# Master.net
KiCad netlist of a schematic drawn in EAGLE
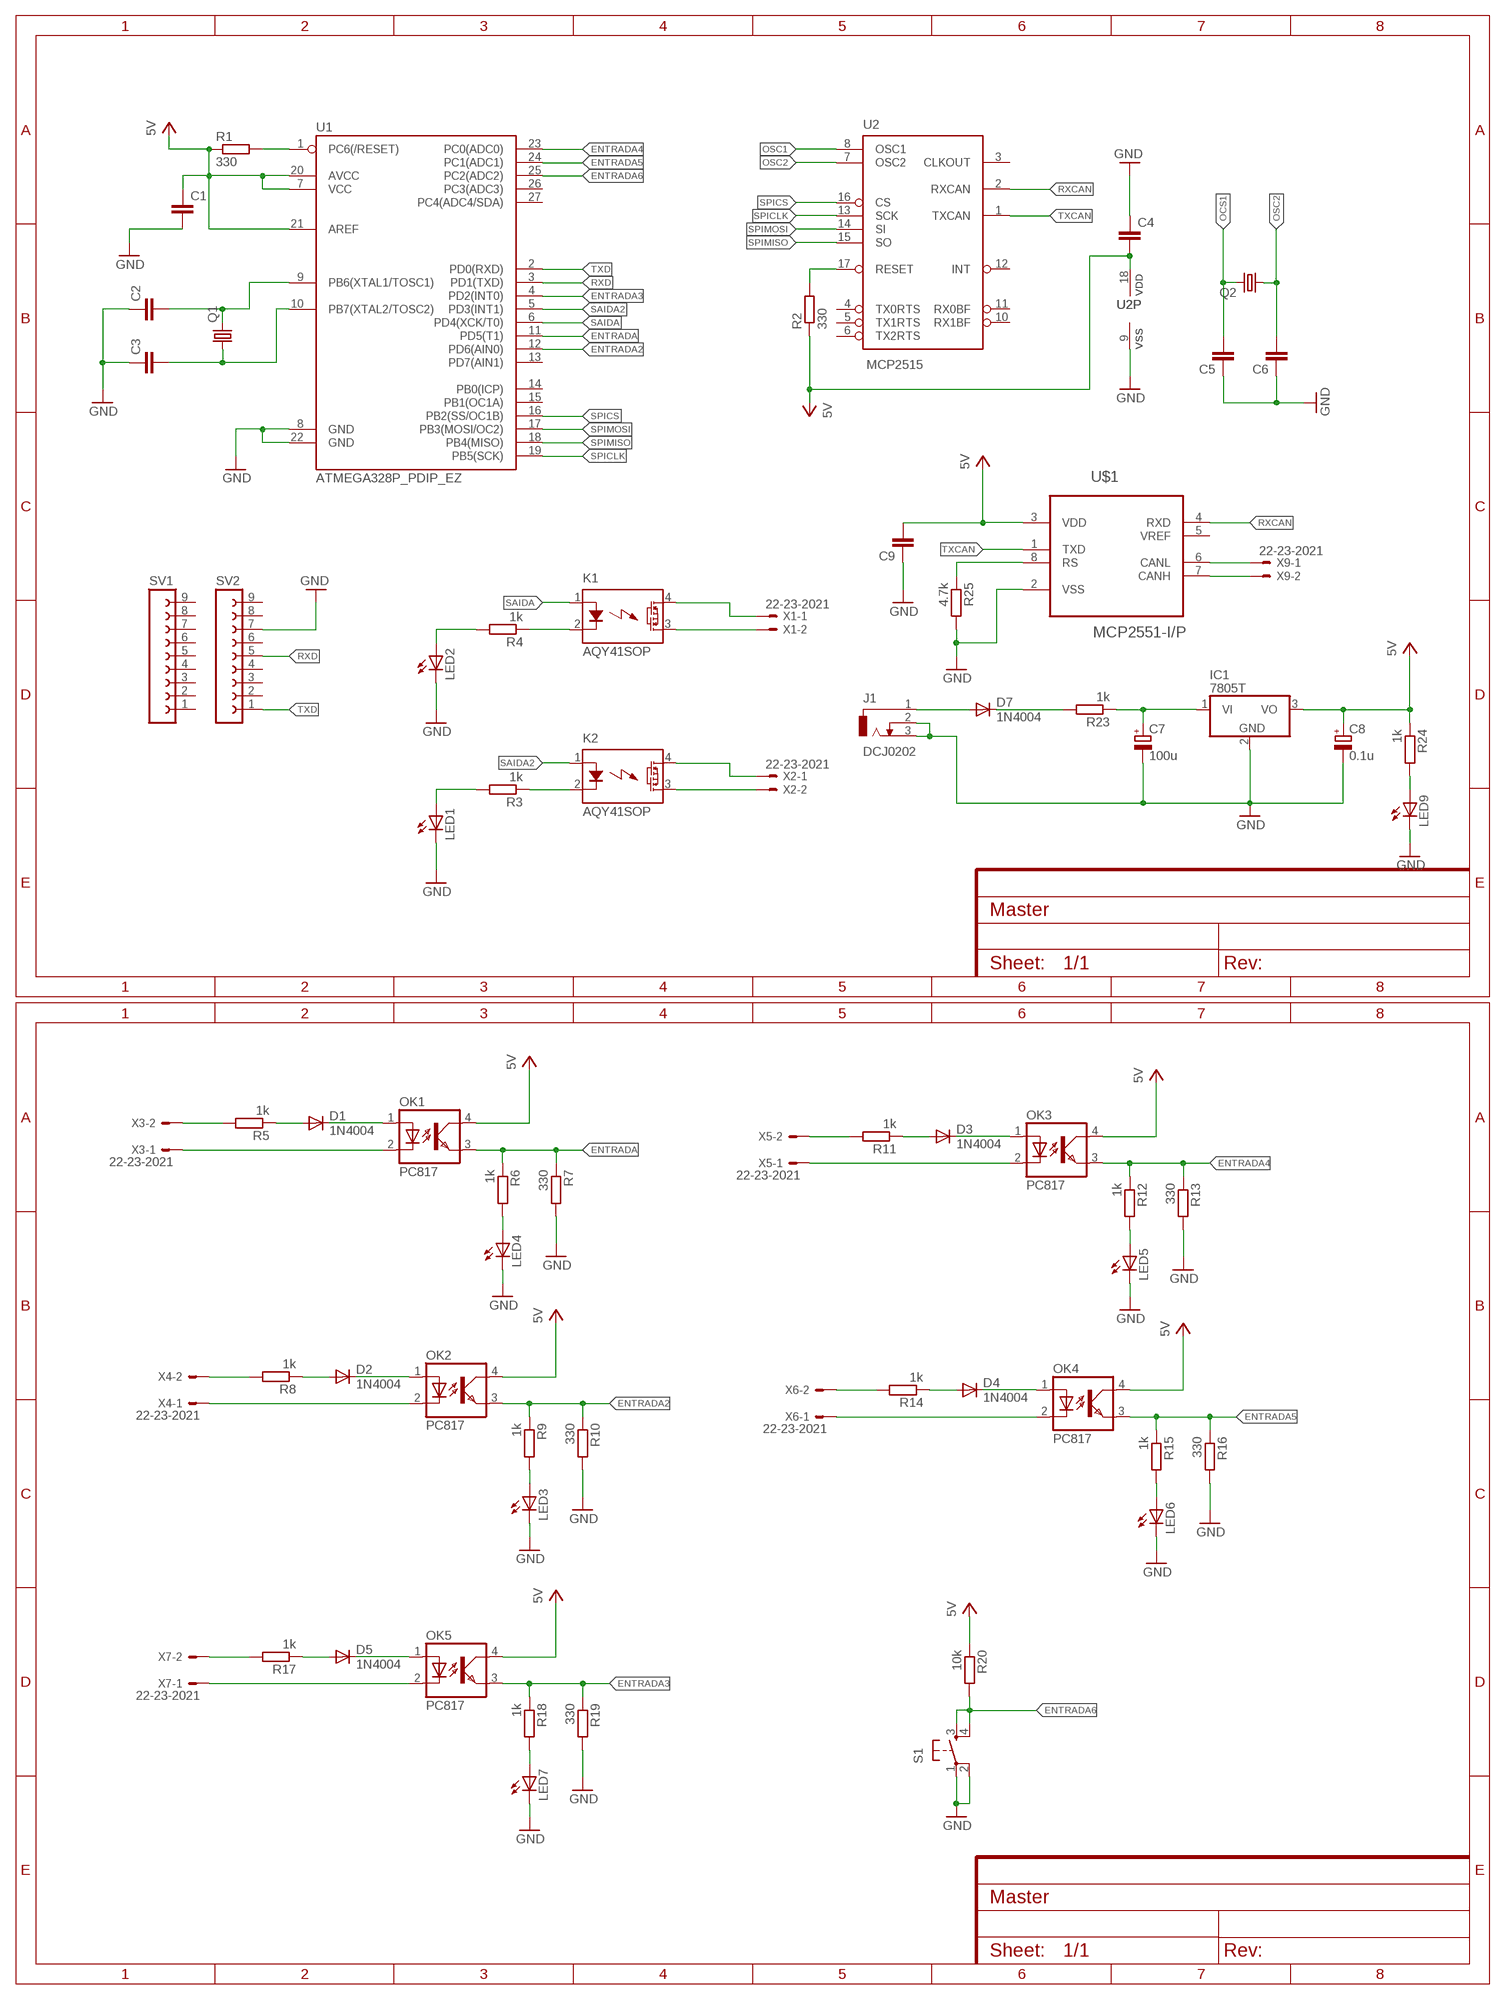
[diagram p0: schematic, sheet 1]

(export (version "E")
  (design (tool "Eeschema 10.0.6"))
  (components
    (comp (ref "C1")
      (value "C2,5-3")
      (footprint "eagle-import:C2.5-3")
      (libsource (lib "eagle-import") (part "C2,5-3"))
    )
    (comp (ref "C2")
      (value "C2,5-3")
      (footprint "eagle-import:C2.5-3")
      (libsource (lib "eagle-import") (part "C2,5-3"))
    )
    (comp (ref "C3")
      (value "C2,5-3")
      (footprint "eagle-import:C2.5-3")
      (libsource (lib "eagle-import") (part "C2,5-3"))
    )
    (comp (ref "C4")
      (value "C2,5-3")
      (footprint "eagle-import:C2.5-3")
      (libsource (lib "eagle-import") (part "C2,5-3"))
    )
    (comp (ref "C5")
      (value "C2,5-3")
      (footprint "eagle-import:C2.5-3")
      (libsource (lib "eagle-import") (part "C2,5-3"))
    )
    (comp (ref "C6")
      (value "C2,5-3")
      (footprint "eagle-import:C2.5-3")
      (libsource (lib "eagle-import") (part "C2,5-3"))
    )
    (comp (ref "C7")
      (value "100u")
      (footprint "eagle-import:E2,5-6")
      (libsource (lib "eagle-import") (part "CPOL-EUE2.5-6"))
    )
    (comp (ref "C8")
      (value "0.1u")
      (footprint "eagle-import:E2,5-6")
      (libsource (lib "eagle-import") (part "CPOL-EUE2.5-6"))
    )
    (comp (ref "C9")
      (value "C2,5-3")
      (footprint "eagle-import:C2.5-3")
      (libsource (lib "eagle-import") (part "C2,5-3"))
    )
    (comp (ref "D1")
      (value "1N4004")
      (footprint "eagle-import:DO41-10")
      (libsource (lib "eagle-import") (part "1N4004"))
    )
    (comp (ref "D2")
      (value "1N4004")
      (footprint "eagle-import:DO41-10")
      (libsource (lib "eagle-import") (part "1N4004"))
    )
    (comp (ref "D3")
      (value "1N4004")
      (footprint "eagle-import:DO41-10")
      (libsource (lib "eagle-import") (part "1N4004"))
    )
    (comp (ref "D4")
      (value "1N4004")
      (footprint "eagle-import:DO41-10")
      (libsource (lib "eagle-import") (part "1N4004"))
    )
    (comp (ref "D5")
      (value "1N4004")
      (footprint "eagle-import:DO41-10")
      (libsource (lib "eagle-import") (part "1N4004"))
    )
    (comp (ref "D7")
      (value "1N4004")
      (footprint "eagle-import:DO41-10")
      (libsource (lib "eagle-import") (part "1N4004"))
    )
    (comp (ref "IC1")
      (value "7805T")
      (footprint "eagle-import:TO220H")
      (libsource (lib "eagle-import") (part "78T05"))
    )
    (comp (ref "J1")
      (value "DCJ0202")
      (footprint "eagle-import:DCJ0202")
      (libsource (lib "eagle-import") (part "DCJ0202"))
    )
    (comp (ref "K1")
      (value "AQY41SOP")
      (footprint "eagle-import:SOP04")
      (libsource (lib "eagle-import") (part "AQYSOP41"))
    )
    (comp (ref "K2")
      (value "AQY41SOP")
      (footprint "eagle-import:SOP04")
      (libsource (lib "eagle-import") (part "AQYSOP41"))
    )
    (comp (ref "LED1")
      (value "LED_ELD260")
      (footprint "eagle-import:LED_LD260")
      (libsource (lib "eagle-import") (part "LED_ELD260"))
    )
    (comp (ref "LED2")
      (value "LED_ELD260")
      (footprint "eagle-import:LED_LD260")
      (libsource (lib "eagle-import") (part "LED_ELD260"))
    )
    (comp (ref "LED3")
      (value "LED_ELD260")
      (footprint "eagle-import:LED_LD260")
      (libsource (lib "eagle-import") (part "LED_ELD260"))
    )
    (comp (ref "LED4")
      (value "LED_ELD260")
      (footprint "eagle-import:LED_LD260")
      (libsource (lib "eagle-import") (part "LED_ELD260"))
    )
    (comp (ref "LED5")
      (value "LED_ELD260")
      (footprint "eagle-import:LED_LD260")
      (libsource (lib "eagle-import") (part "LED_ELD260"))
    )
    (comp (ref "LED6")
      (value "LED_ELD260")
      (footprint "eagle-import:LED_LD260")
      (libsource (lib "eagle-import") (part "LED_ELD260"))
    )
    (comp (ref "LED7")
      (value "LED_ELD260")
      (footprint "eagle-import:LED_LD260")
      (libsource (lib "eagle-import") (part "LED_ELD260"))
    )
    (comp (ref "LED9")
      (value "LED_ELD260")
      (footprint "eagle-import:LED_LD260")
      (libsource (lib "eagle-import") (part "LED_ELD260"))
    )
    (comp (ref "OK1")
      (value "PC817")
      (footprint "eagle-import:DIL04")
      (fields (field (name "MPN") "PC817X4J000F"))
      (libsource (lib "eagle-import") (part "PC817"))
    )
    (comp (ref "OK2")
      (value "PC817")
      (footprint "eagle-import:DIL04")
      (fields (field (name "MPN") "PC817X4J000F"))
      (libsource (lib "eagle-import") (part "PC817"))
    )
    (comp (ref "OK3")
      (value "PC817")
      (footprint "eagle-import:DIL04")
      (fields (field (name "MPN") "PC817X4J000F"))
      (libsource (lib "eagle-import") (part "PC817"))
    )
    (comp (ref "OK4")
      (value "PC817")
      (footprint "eagle-import:DIL04")
      (fields (field (name "MPN") "PC817X4J000F"))
      (libsource (lib "eagle-import") (part "PC817"))
    )
    (comp (ref "OK5")
      (value "PC817")
      (footprint "eagle-import:DIL04")
      (fields (field (name "MPN") "PC817X4J000F"))
      (libsource (lib "eagle-import") (part "PC817"))
    )
    (comp (ref "Q1")
      (value "CRYSTALHC49U70")
      (footprint "eagle-import:HC49U70")
      (libsource (lib "eagle-import") (part "CRYSTALHC49U70"))
    )
    (comp (ref "Q2")
      (value "CRYSTALHC49U70")
      (footprint "eagle-import:HC49U70")
      (libsource (lib "eagle-import") (part "CRYSTALHC49U70"))
    )
    (comp (ref "R1")
      (value "330")
      (footprint "eagle-import:0204_5")
      (libsource (lib "eagle-import") (part "R-EU_0204/5"))
    )
    (comp (ref "R2")
      (value "330")
      (footprint "eagle-import:0204_5")
      (libsource (lib "eagle-import") (part "R-EU_0204/5"))
    )
    (comp (ref "R3")
      (value "1k")
      (footprint "eagle-import:0204_5")
      (libsource (lib "eagle-import") (part "R-EU_0204/5"))
    )
    (comp (ref "R4")
      (value "1k")
      (footprint "eagle-import:0204_5")
      (libsource (lib "eagle-import") (part "R-EU_0204/5"))
    )
    (comp (ref "R5")
      (value "1k")
      (footprint "eagle-import:0204_5")
      (libsource (lib "eagle-import") (part "R-EU_0204/5"))
    )
    (comp (ref "R6")
      (value "1k")
      (footprint "eagle-import:0204_5")
      (libsource (lib "eagle-import") (part "R-EU_0204/5"))
    )
    (comp (ref "R7")
      (value "330")
      (footprint "eagle-import:0204_5")
      (libsource (lib "eagle-import") (part "R-EU_0204/5"))
    )
    (comp (ref "R8")
      (value "1k")
      (footprint "eagle-import:0204_5")
      (libsource (lib "eagle-import") (part "R-EU_0204/5"))
    )
    (comp (ref "R9")
      (value "1k")
      (footprint "eagle-import:0204_5")
      (libsource (lib "eagle-import") (part "R-EU_0204/5"))
    )
    (comp (ref "R10")
      (value "330")
      (footprint "eagle-import:0204_5")
      (libsource (lib "eagle-import") (part "R-EU_0204/5"))
    )
    (comp (ref "R11")
      (value "1k")
      (footprint "eagle-import:0204_5")
      (libsource (lib "eagle-import") (part "R-EU_0204/5"))
    )
    (comp (ref "R12")
      (value "1k")
      (footprint "eagle-import:0204_5")
      (libsource (lib "eagle-import") (part "R-EU_0204/5"))
    )
    (comp (ref "R13")
      (value "330")
      (footprint "eagle-import:0204_5")
      (libsource (lib "eagle-import") (part "R-EU_0204/5"))
    )
    (comp (ref "R14")
      (value "1k")
      (footprint "eagle-import:0204_5")
      (libsource (lib "eagle-import") (part "R-EU_0204/5"))
    )
    (comp (ref "R15")
      (value "1k")
      (footprint "eagle-import:0204_5")
      (libsource (lib "eagle-import") (part "R-EU_0204/5"))
    )
    (comp (ref "R16")
      (value "330")
      (footprint "eagle-import:0204_5")
      (libsource (lib "eagle-import") (part "R-EU_0204/5"))
    )
    (comp (ref "R17")
      (value "1k")
      (footprint "eagle-import:0204_5")
      (libsource (lib "eagle-import") (part "R-EU_0204/5"))
    )
    (comp (ref "R18")
      (value "1k")
      (footprint "eagle-import:0204_5")
      (libsource (lib "eagle-import") (part "R-EU_0204/5"))
    )
    (comp (ref "R19")
      (value "330")
      (footprint "eagle-import:0204_5")
      (libsource (lib "eagle-import") (part "R-EU_0204/5"))
    )
    (comp (ref "R20")
      (value "10k")
      (footprint "eagle-import:0204_5")
      (libsource (lib "eagle-import") (part "R-EU_0204/5"))
    )
    (comp (ref "R23")
      (value "1k")
      (footprint "eagle-import:0204_5")
      (libsource (lib "eagle-import") (part "R-EU_0204/5"))
    )
    (comp (ref "R24")
      (value "1k")
      (footprint "eagle-import:0204_5")
      (libsource (lib "eagle-import") (part "R-EU_0204/5"))
    )
    (comp (ref "R25")
      (value "4.7k")
      (footprint "eagle-import:0204_5")
      (libsource (lib "eagle-import") (part "R-EU_0204/5"))
    )
    (comp (ref "S1")
      (value "TAC_SWITCHPTH")
      (footprint "eagle-import:TACTILE-PTH")
      (libsource (lib "eagle-import") (part "TAC_SWITCHPTH"))
    )
    (comp (ref "SV1")
      (value "FE09-1")
      (footprint "eagle-import:FE09")
      (libsource (lib "eagle-import") (part "FE09-1"))
    )
    (comp (ref "SV2")
      (value "FE09-1")
      (footprint "eagle-import:FE09")
      (libsource (lib "eagle-import") (part "FE09-1"))
    )
    (comp (ref "U$1")
      (value "MCP2551-I/P")
      (footprint "eagle-import:DIP254P762X432-8")
      (libsource (lib "eagle-import") (part "MCP2551-I/P"))
    )
    (comp (ref "U1")
      (value "ATMEGA328P_PDIP_EZ")
      (footprint "eagle-import:DIP28-SIMON-KIT")
      (libsource (lib "eagle-import") (part "ATMEGA328P_PDIP_EZ"))
    )
    (comp (ref "U2")
      (value "MCP2515")
      (footprint "eagle-import:DIP18")
      (libsource (lib "eagle-import") (part "MCP2515(MCP2510)P"))
    )
    (comp (ref "X1")
      (value "22-23-2021")
      (footprint "eagle-import:22-23-2021")
      (fields (field (name "MF") "MOLEX"))
      (libsource (lib "eagle-import") (part "22-23-2021"))
    )
    (comp (ref "X2")
      (value "22-23-2021")
      (footprint "eagle-import:22-23-2021")
      (fields (field (name "MF") "MOLEX"))
      (libsource (lib "eagle-import") (part "22-23-2021"))
    )
    (comp (ref "X3")
      (value "22-23-2021")
      (footprint "eagle-import:22-23-2021")
      (fields (field (name "MF") "MOLEX"))
      (libsource (lib "eagle-import") (part "22-23-2021"))
    )
    (comp (ref "X4")
      (value "22-23-2021")
      (footprint "eagle-import:22-23-2021")
      (fields (field (name "MF") "MOLEX"))
      (libsource (lib "eagle-import") (part "22-23-2021"))
    )
    (comp (ref "X5")
      (value "22-23-2021")
      (footprint "eagle-import:22-23-2021")
      (fields (field (name "MF") "MOLEX"))
      (libsource (lib "eagle-import") (part "22-23-2021"))
    )
    (comp (ref "X6")
      (value "22-23-2021")
      (footprint "eagle-import:22-23-2021")
      (fields (field (name "MF") "MOLEX"))
      (libsource (lib "eagle-import") (part "22-23-2021"))
    )
    (comp (ref "X7")
      (value "22-23-2021")
      (footprint "eagle-import:22-23-2021")
      (fields (field (name "MF") "MOLEX"))
      (libsource (lib "eagle-import") (part "22-23-2021"))
    )
    (comp (ref "X9")
      (value "22-23-2021")
      (footprint "eagle-import:22-23-2021")
      (fields (field (name "MF") "MOLEX"))
      (libsource (lib "eagle-import") (part "22-23-2021"))
    )
  )
  (nets
    (net (code "1") (name "5V") (class "Default")
      (node (ref "C1") (pin "1") (pinfunction "1_1") (pintype "passive"))
      (node (ref "C4") (pin "2") (pinfunction "2_2") (pintype "passive"))
      (node (ref "C8") (pin "+") (pinfunction "+_+") (pintype "passive"))
      (node (ref "C9") (pin "2") (pinfunction "2_2") (pintype "passive"))
      (node (ref "IC1") (pin "3") (pinfunction "VO_3") (pintype "passive"))
      (node (ref "OK1") (pin "4") (pinfunction "COL_4") (pintype "passive"))
      (node (ref "OK2") (pin "4") (pinfunction "COL_4") (pintype "passive"))
      (node (ref "OK3") (pin "4") (pinfunction "COL_4") (pintype "passive"))
      (node (ref "OK4") (pin "4") (pinfunction "COL_4") (pintype "passive"))
      (node (ref "OK5") (pin "4") (pinfunction "COL_4") (pintype "passive"))
      (node (ref "R1") (pin "1") (pinfunction "1_1") (pintype "passive"))
      (node (ref "R2") (pin "1") (pinfunction "1_1") (pintype "passive"))
      (node (ref "R20") (pin "1") (pinfunction "1_1") (pintype "passive"))
      (node (ref "R24") (pin "1") (pinfunction "1_1") (pintype "passive"))
      (node (ref "U$1") (pin "3") (pinfunction "VDD_3") (pintype "power_in"))
      (node (ref "U1") (pin "20") (pinfunction "AVCC_20") (pintype "bidirectional"))
      (node (ref "U1") (pin "21") (pinfunction "AREF_21") (pintype "bidirectional"))
      (node (ref "U1") (pin "7") (pinfunction "VCC_7") (pintype "bidirectional"))
      (node (ref "U2") (pin "18") (pinfunction "VDD_18") (pintype "power_in"))
    )
    (net (code "2") (name "ENTRADA") (class "Default")
      (node (ref "OK1") (pin "3") (pinfunction "EMIT_3") (pintype "passive"))
      (node (ref "R6") (pin "1") (pinfunction "1_1") (pintype "passive"))
      (node (ref "R7") (pin "1") (pinfunction "1_1") (pintype "passive"))
      (node (ref "U1") (pin "11") (pinfunction "PD5(T1)_11") (pintype "bidirectional"))
    )
    (net (code "3") (name "ENTRADA2") (class "Default")
      (node (ref "OK2") (pin "3") (pinfunction "EMIT_3") (pintype "passive"))
      (node (ref "R10") (pin "1") (pinfunction "1_1") (pintype "passive"))
      (node (ref "R9") (pin "1") (pinfunction "1_1") (pintype "passive"))
      (node (ref "U1") (pin "12") (pinfunction "PD6(AIN0)_12") (pintype "bidirectional"))
    )
    (net (code "4") (name "ENTRADA3") (class "Default")
      (node (ref "OK5") (pin "3") (pinfunction "EMIT_3") (pintype "passive"))
      (node (ref "R18") (pin "1") (pinfunction "1_1") (pintype "passive"))
      (node (ref "R19") (pin "1") (pinfunction "1_1") (pintype "passive"))
      (node (ref "U1") (pin "4") (pinfunction "PD2(INT0)_4") (pintype "bidirectional"))
    )
    (net (code "5") (name "ENTRADA4") (class "Default")
      (node (ref "OK3") (pin "3") (pinfunction "EMIT_3") (pintype "passive"))
      (node (ref "R12") (pin "1") (pinfunction "1_1") (pintype "passive"))
      (node (ref "R13") (pin "1") (pinfunction "1_1") (pintype "passive"))
      (node (ref "U1") (pin "23") (pinfunction "PC0(ADC0)_23") (pintype "bidirectional"))
    )
    (net (code "6") (name "ENTRADA5") (class "Default")
      (node (ref "OK4") (pin "3") (pinfunction "EMIT_3") (pintype "passive"))
      (node (ref "R15") (pin "1") (pinfunction "1_1") (pintype "passive"))
      (node (ref "R16") (pin "1") (pinfunction "1_1") (pintype "passive"))
      (node (ref "U1") (pin "24") (pinfunction "PC1(ADC1)_24") (pintype "bidirectional"))
    )
    (net (code "7") (name "ENTRADA6") (class "Default")
      (node (ref "R20") (pin "2") (pinfunction "2_2") (pintype "passive"))
      (node (ref "S1") (pin "3") (pinfunction "3_3") (pintype "passive"))
      (node (ref "S1") (pin "4") (pinfunction "4_4") (pintype "passive"))
      (node (ref "U1") (pin "25") (pinfunction "PC2(ADC2)_25") (pintype "bidirectional"))
    )
    (net (code "8") (name "GND") (class "Default")
      (node (ref "C1") (pin "2") (pinfunction "2_2") (pintype "passive"))
      (node (ref "C2") (pin "1") (pinfunction "1_1") (pintype "passive"))
      (node (ref "C3") (pin "1") (pinfunction "1_1") (pintype "passive"))
      (node (ref "C4") (pin "1") (pinfunction "1_1") (pintype "passive"))
      (node (ref "C5") (pin "1") (pinfunction "1_1") (pintype "passive"))
      (node (ref "C6") (pin "1") (pinfunction "1_1") (pintype "passive"))
      (node (ref "C7") (pin "-") (pinfunction "-_-") (pintype "passive"))
      (node (ref "C8") (pin "-") (pinfunction "-_-") (pintype "passive"))
      (node (ref "C9") (pin "1") (pinfunction "1_1") (pintype "passive"))
      (node (ref "IC1") (pin "2") (pinfunction "GND_2") (pintype "passive"))
      (node (ref "J1") (pin "2") (pinfunction "2_2") (pintype "passive"))
      (node (ref "J1") (pin "3") (pinfunction "3_3") (pintype "passive"))
      (node (ref "LED1") (pin "K") (pinfunction "C_K") (pintype "passive"))
      (node (ref "LED2") (pin "K") (pinfunction "C_K") (pintype "passive"))
      (node (ref "LED3") (pin "K") (pinfunction "C_K") (pintype "passive"))
      (node (ref "LED4") (pin "K") (pinfunction "C_K") (pintype "passive"))
      (node (ref "LED5") (pin "K") (pinfunction "C_K") (pintype "passive"))
      (node (ref "LED6") (pin "K") (pinfunction "C_K") (pintype "passive"))
      (node (ref "LED7") (pin "K") (pinfunction "C_K") (pintype "passive"))
      (node (ref "LED9") (pin "K") (pinfunction "C_K") (pintype "passive"))
      (node (ref "R10") (pin "2") (pinfunction "2_2") (pintype "passive"))
      (node (ref "R13") (pin "2") (pinfunction "2_2") (pintype "passive"))
      (node (ref "R16") (pin "2") (pinfunction "2_2") (pintype "passive"))
      (node (ref "R19") (pin "2") (pinfunction "2_2") (pintype "passive"))
      (node (ref "R25") (pin "2") (pinfunction "2_2") (pintype "passive"))
      (node (ref "R7") (pin "2") (pinfunction "2_2") (pintype "passive"))
      (node (ref "S1") (pin "1") (pinfunction "1_1") (pintype "passive"))
      (node (ref "S1") (pin "2") (pinfunction "2_2") (pintype "passive"))
      (node (ref "SV2") (pin "7") (pinfunction "7_7") (pintype "passive"))
      (node (ref "U$1") (pin "2") (pinfunction "VSS_2") (pintype "power_in"))
      (node (ref "U1") (pin "22") (pinfunction "GND_22") (pintype "bidirectional"))
      (node (ref "U1") (pin "8") (pinfunction "GND_8") (pintype "bidirectional"))
      (node (ref "U2") (pin "9") (pinfunction "VSS_9") (pintype "power_in"))
    )
    (net (code "9") (name "Net-(D1-PadA)") (class "Default")
      (node (ref "D1") (pin "A") (pinfunction "A_A") (pintype "passive"))
      (node (ref "R5") (pin "1") (pinfunction "1_1") (pintype "passive"))
    )
    (net (code "10") (name "Net-(D2-PadA)") (class "Default")
      (node (ref "D2") (pin "A") (pinfunction "A_A") (pintype "passive"))
      (node (ref "R8") (pin "1") (pinfunction "1_1") (pintype "passive"))
    )
    (net (code "11") (name "Net-(D3-PadA)") (class "Default")
      (node (ref "D3") (pin "A") (pinfunction "A_A") (pintype "passive"))
      (node (ref "R11") (pin "1") (pinfunction "1_1") (pintype "passive"))
    )
    (net (code "12") (name "Net-(D4-PadA)") (class "Default")
      (node (ref "D4") (pin "A") (pinfunction "A_A") (pintype "passive"))
      (node (ref "R14") (pin "1") (pinfunction "1_1") (pintype "passive"))
    )
    (net (code "13") (name "Net-(D5-PadA)") (class "Default")
      (node (ref "D5") (pin "A") (pinfunction "A_A") (pintype "passive"))
      (node (ref "R17") (pin "1") (pinfunction "1_1") (pintype "passive"))
    )
    (net (code "14") (name "Net-(D7-PadA)") (class "Default")
      (node (ref "D7") (pin "A") (pinfunction "A_A") (pintype "passive"))
      (node (ref "J1") (pin "1") (pinfunction "1_1") (pintype "passive"))
    )
    (net (code "15") (name "Net-(D7-PadC)") (class "Default")
      (node (ref "D7") (pin "C") (pinfunction "C_C") (pintype "passive"))
      (node (ref "R23") (pin "2") (pinfunction "2_2") (pintype "passive"))
    )
    (net (code "16") (name "Net-(IC1-VI)") (class "Default")
      (node (ref "C7") (pin "+") (pinfunction "+_+") (pintype "passive"))
      (node (ref "IC1") (pin "1") (pinfunction "VI_1") (pintype "input"))
      (node (ref "R23") (pin "1") (pinfunction "1_1") (pintype "passive"))
    )
    (net (code "17") (name "Net-(K1-DS1)") (class "Default")
      (node (ref "K1") (pin "4") (pinfunction "DS1_4") (pintype "passive"))
      (node (ref "X1") (pin "1") (pinfunction "S_1") (pintype "passive"))
    )
    (net (code "18") (name "Net-(K1-DS2)") (class "Default")
      (node (ref "K1") (pin "3") (pinfunction "DS2_3") (pintype "passive"))
      (node (ref "X1") (pin "2") (pinfunction "S_2") (pintype "passive"))
    )
    (net (code "19") (name "Net-(K1-K)") (class "Default")
      (node (ref "K1") (pin "2") (pinfunction "K_2") (pintype "passive"))
      (node (ref "R4") (pin "1") (pinfunction "1_1") (pintype "passive"))
    )
    (net (code "20") (name "Net-(K2-DS1)") (class "Default")
      (node (ref "K2") (pin "4") (pinfunction "DS1_4") (pintype "passive"))
      (node (ref "X2") (pin "1") (pinfunction "S_1") (pintype "passive"))
    )
    (net (code "21") (name "Net-(K2-DS2)") (class "Default")
      (node (ref "K2") (pin "3") (pinfunction "DS2_3") (pintype "passive"))
      (node (ref "X2") (pin "2") (pinfunction "S_2") (pintype "passive"))
    )
    (net (code "22") (name "Net-(K2-K)") (class "Default")
      (node (ref "K2") (pin "2") (pinfunction "K_2") (pintype "passive"))
      (node (ref "R3") (pin "1") (pinfunction "1_1") (pintype "passive"))
    )
    (net (code "23") (name "Net-(LED1-PadA)") (class "Default")
      (node (ref "LED1") (pin "A") (pinfunction "A_A") (pintype "passive"))
      (node (ref "R3") (pin "2") (pinfunction "2_2") (pintype "passive"))
    )
    (net (code "24") (name "Net-(LED2-PadA)") (class "Default")
      (node (ref "LED2") (pin "A") (pinfunction "A_A") (pintype "passive"))
      (node (ref "R4") (pin "2") (pinfunction "2_2") (pintype "passive"))
    )
    (net (code "25") (name "Net-(LED3-PadA)") (class "Default")
      (node (ref "LED3") (pin "A") (pinfunction "A_A") (pintype "passive"))
      (node (ref "R9") (pin "2") (pinfunction "2_2") (pintype "passive"))
    )
    (net (code "26") (name "Net-(LED4-PadA)") (class "Default")
      (node (ref "LED4") (pin "A") (pinfunction "A_A") (pintype "passive"))
      (node (ref "R6") (pin "2") (pinfunction "2_2") (pintype "passive"))
    )
    (net (code "27") (name "Net-(LED5-PadA)") (class "Default")
      (node (ref "LED5") (pin "A") (pinfunction "A_A") (pintype "passive"))
      (node (ref "R12") (pin "2") (pinfunction "2_2") (pintype "passive"))
    )
    (net (code "28") (name "Net-(LED6-PadA)") (class "Default")
      (node (ref "LED6") (pin "A") (pinfunction "A_A") (pintype "passive"))
      (node (ref "R15") (pin "2") (pinfunction "2_2") (pintype "passive"))
    )
    (net (code "29") (name "Net-(LED7-PadA)") (class "Default")
      (node (ref "LED7") (pin "A") (pinfunction "A_A") (pintype "passive"))
      (node (ref "R18") (pin "2") (pinfunction "2_2") (pintype "passive"))
    )
    (net (code "30") (name "Net-(LED9-PadA)") (class "Default")
      (node (ref "LED9") (pin "A") (pinfunction "A_A") (pintype "passive"))
      (node (ref "R24") (pin "2") (pinfunction "2_2") (pintype "passive"))
    )
    (net (code "31") (name "Net-(OK1-A)") (class "Default")
      (node (ref "D1") (pin "C") (pinfunction "C_C") (pintype "passive"))
      (node (ref "OK1") (pin "1") (pinfunction "A_1") (pintype "passive"))
    )
    (net (code "32") (name "Net-(OK1-C)") (class "Default")
      (node (ref "OK1") (pin "2") (pinfunction "C_2") (pintype "passive"))
      (node (ref "X3") (pin "1") (pinfunction "S_1") (pintype "passive"))
    )
    (net (code "33") (name "Net-(OK2-A)") (class "Default")
      (node (ref "D2") (pin "C") (pinfunction "C_C") (pintype "passive"))
      (node (ref "OK2") (pin "1") (pinfunction "A_1") (pintype "passive"))
    )
    (net (code "34") (name "Net-(OK2-C)") (class "Default")
      (node (ref "OK2") (pin "2") (pinfunction "C_2") (pintype "passive"))
      (node (ref "X4") (pin "1") (pinfunction "S_1") (pintype "passive"))
    )
    (net (code "35") (name "Net-(OK3-A)") (class "Default")
      (node (ref "D3") (pin "C") (pinfunction "C_C") (pintype "passive"))
      (node (ref "OK3") (pin "1") (pinfunction "A_1") (pintype "passive"))
    )
    (net (code "36") (name "Net-(OK3-C)") (class "Default")
      (node (ref "OK3") (pin "2") (pinfunction "C_2") (pintype "passive"))
      (node (ref "X5") (pin "1") (pinfunction "S_1") (pintype "passive"))
    )
    (net (code "37") (name "Net-(OK4-A)") (class "Default")
      (node (ref "D4") (pin "C") (pinfunction "C_C") (pintype "passive"))
      (node (ref "OK4") (pin "1") (pinfunction "A_1") (pintype "passive"))
    )
    (net (code "38") (name "Net-(OK4-C)") (class "Default")
      (node (ref "OK4") (pin "2") (pinfunction "C_2") (pintype "passive"))
      (node (ref "X6") (pin "1") (pinfunction "S_1") (pintype "passive"))
    )
    (net (code "39") (name "Net-(OK5-A)") (class "Default")
      (node (ref "D5") (pin "C") (pinfunction "C_C") (pintype "passive"))
      (node (ref "OK5") (pin "1") (pinfunction "A_1") (pintype "passive"))
    )
    (net (code "40") (name "Net-(OK5-C)") (class "Default")
      (node (ref "OK5") (pin "2") (pinfunction "C_2") (pintype "passive"))
      (node (ref "X7") (pin "1") (pinfunction "S_1") (pintype "passive"))
    )
    (net (code "41") (name "Net-(U$1-CANH)") (class "Default")
      (node (ref "U$1") (pin "7") (pinfunction "CANH_7") (pintype "bidirectional"))
      (node (ref "X9") (pin "2") (pinfunction "S_2") (pintype "passive"))
    )
    (net (code "42") (name "Net-(U$1-CANL)") (class "Default")
      (node (ref "U$1") (pin "6") (pinfunction "CANL_6") (pintype "bidirectional"))
      (node (ref "X9") (pin "1") (pinfunction "S_1") (pintype "passive"))
    )
    (net (code "43") (name "Net-(U$1-RS)") (class "Default")
      (node (ref "R25") (pin "1") (pinfunction "1_1") (pintype "passive"))
      (node (ref "U$1") (pin "8") (pinfunction "RS_8") (pintype "input"))
    )
    (net (code "44") (name "Net-(U1-PB6(XTAL1{slash}TOSC1))") (class "Default")
      (node (ref "C2") (pin "2") (pinfunction "2_2") (pintype "passive"))
      (node (ref "Q1") (pin "2") (pinfunction "2_2") (pintype "passive"))
      (node (ref "U1") (pin "9") (pinfunction "PB6(XTAL1/TOSC1)_9") (pintype "bidirectional"))
    )
    (net (code "45") (name "Net-(U1-PB7(XTAL2{slash}TOSC2))") (class "Default")
      (node (ref "C3") (pin "2") (pinfunction "2_2") (pintype "passive"))
      (node (ref "Q1") (pin "1") (pinfunction "1_1") (pintype "passive"))
      (node (ref "U1") (pin "10") (pinfunction "PB7(XTAL2/TOSC2)_10") (pintype "bidirectional"))
    )
    (net (code "46") (name "Net-(U1-PC6({slash}RESET))") (class "Default")
      (node (ref "R1") (pin "2") (pinfunction "2_2") (pintype "passive"))
      (node (ref "U1") (pin "1") (pinfunction "PC6(/RESET)_1") (pintype "bidirectional"))
    )
    (net (code "47") (name "Net-(U2A-RESET)") (class "Default")
      (node (ref "R2") (pin "2") (pinfunction "2_2") (pintype "passive"))
      (node (ref "U2") (pin "17") (pinfunction "RESET_17") (pintype "input"))
    )
    (net (code "48") (name "Net-(X3B-S)") (class "Default")
      (node (ref "R5") (pin "2") (pinfunction "2_2") (pintype "passive"))
      (node (ref "X3") (pin "2") (pinfunction "S_2") (pintype "passive"))
    )
    (net (code "49") (name "Net-(X4B-S)") (class "Default")
      (node (ref "R8") (pin "2") (pinfunction "2_2") (pintype "passive"))
      (node (ref "X4") (pin "2") (pinfunction "S_2") (pintype "passive"))
    )
    (net (code "50") (name "Net-(X5B-S)") (class "Default")
      (node (ref "R11") (pin "2") (pinfunction "2_2") (pintype "passive"))
      (node (ref "X5") (pin "2") (pinfunction "S_2") (pintype "passive"))
    )
    (net (code "51") (name "Net-(X6B-S)") (class "Default")
      (node (ref "R14") (pin "2") (pinfunction "2_2") (pintype "passive"))
      (node (ref "X6") (pin "2") (pinfunction "S_2") (pintype "passive"))
    )
    (net (code "52") (name "Net-(X7B-S)") (class "Default")
      (node (ref "R17") (pin "2") (pinfunction "2_2") (pintype "passive"))
      (node (ref "X7") (pin "2") (pinfunction "S_2") (pintype "passive"))
    )
    (net (code "53") (name "OCS1") (class "Default")
      (node (ref "C5") (pin "2") (pinfunction "2_2") (pintype "passive"))
      (node (ref "Q2") (pin "2") (pinfunction "2_2") (pintype "passive"))
    )
    (net (code "54") (name "OSC1") (class "Default")
      (node (ref "U2") (pin "8") (pinfunction "OSC1_8") (pintype "input"))
    )
    (net (code "55") (name "OSC2") (class "Default")
      (node (ref "C6") (pin "2") (pinfunction "2_2") (pintype "passive"))
      (node (ref "Q2") (pin "1") (pinfunction "1_1") (pintype "passive"))
      (node (ref "U2") (pin "7") (pinfunction "OSC2_7") (pintype "output"))
    )
    (net (code "56") (name "RXCAN") (class "Default")
      (node (ref "U$1") (pin "4") (pinfunction "RXD_4") (pintype "output"))
      (node (ref "U2") (pin "2") (pinfunction "RXCAN_2") (pintype "input"))
    )
    (net (code "57") (name "RXD") (class "Default")
      (node (ref "SV2") (pin "5") (pinfunction "5_5") (pintype "passive"))
      (node (ref "U1") (pin "3") (pinfunction "PD1(TXD)_3") (pintype "bidirectional"))
    )
    (net (code "58") (name "SAIDA") (class "Default")
      (node (ref "K1") (pin "1") (pinfunction "A_1") (pintype "passive"))
      (node (ref "U1") (pin "6") (pinfunction "PD4(XCK/T0)_6") (pintype "bidirectional"))
    )
    (net (code "59") (name "SAIDA2") (class "Default")
      (node (ref "K2") (pin "1") (pinfunction "A_1") (pintype "passive"))
      (node (ref "U1") (pin "5") (pinfunction "PD3(INT1)_5") (pintype "bidirectional"))
    )
    (net (code "60") (name "SPICLK") (class "Default")
      (node (ref "U1") (pin "19") (pinfunction "PB5(SCK)_19") (pintype "bidirectional"))
      (node (ref "U2") (pin "13") (pinfunction "SCK_13") (pintype "input"))
    )
    (net (code "61") (name "SPICS") (class "Default")
      (node (ref "U1") (pin "16") (pinfunction "PB2(SS/OC1B)_16") (pintype "bidirectional"))
      (node (ref "U2") (pin "16") (pinfunction "CS_16") (pintype "input"))
    )
    (net (code "62") (name "SPIMISO") (class "Default")
      (node (ref "U1") (pin "18") (pinfunction "PB4(MISO)_18") (pintype "bidirectional"))
      (node (ref "U2") (pin "15") (pinfunction "SO_15") (pintype "output"))
    )
    (net (code "63") (name "SPIMOSI") (class "Default")
      (node (ref "U1") (pin "17") (pinfunction "PB3(MOSI/OC2)_17") (pintype "bidirectional"))
      (node (ref "U2") (pin "14") (pinfunction "SI_14") (pintype "input"))
    )
    (net (code "64") (name "TXCAN") (class "Default")
      (node (ref "U$1") (pin "1") (pinfunction "TXD_1") (pintype "input"))
      (node (ref "U2") (pin "1") (pinfunction "TXCAN_1") (pintype "output"))
    )
    (net (code "65") (name "TXD") (class "Default")
      (node (ref "SV2") (pin "1") (pinfunction "1_1") (pintype "passive"))
      (node (ref "U1") (pin "2") (pinfunction "PD0(RXD)_2") (pintype "bidirectional"))
    )
    (net (code "66") (name "unconnected-(SV1-Pad1)") (class "Default")
      (node (ref "SV1") (pin "1") (pinfunction "1_1") (pintype "passive"))
    )
    (net (code "67") (name "unconnected-(SV1-Pad2)") (class "Default")
      (node (ref "SV1") (pin "2") (pinfunction "2_2") (pintype "passive"))
    )
    (net (code "68") (name "unconnected-(SV1-Pad3)") (class "Default")
      (node (ref "SV1") (pin "3") (pinfunction "3_3") (pintype "passive"))
    )
    (net (code "69") (name "unconnected-(SV1-Pad4)") (class "Default")
      (node (ref "SV1") (pin "4") (pinfunction "4_4") (pintype "passive"))
    )
    (net (code "70") (name "unconnected-(SV1-Pad5)") (class "Default")
      (node (ref "SV1") (pin "5") (pinfunction "5_5") (pintype "passive"))
    )
    (net (code "71") (name "unconnected-(SV1-Pad6)") (class "Default")
      (node (ref "SV1") (pin "6") (pinfunction "6_6") (pintype "passive"))
    )
    (net (code "72") (name "unconnected-(SV1-Pad7)") (class "Default")
      (node (ref "SV1") (pin "7") (pinfunction "7_7") (pintype "passive"))
    )
    (net (code "73") (name "unconnected-(SV1-Pad8)") (class "Default")
      (node (ref "SV1") (pin "8") (pinfunction "8_8") (pintype "passive"))
    )
    (net (code "74") (name "unconnected-(SV1-Pad9)") (class "Default")
      (node (ref "SV1") (pin "9") (pinfunction "9_9") (pintype "passive"))
    )
    (net (code "75") (name "unconnected-(SV2-Pad2)") (class "Default")
      (node (ref "SV2") (pin "2") (pinfunction "2_2") (pintype "passive"))
    )
    (net (code "76") (name "unconnected-(SV2-Pad3)") (class "Default")
      (node (ref "SV2") (pin "3") (pinfunction "3_3") (pintype "passive"))
    )
    (net (code "77") (name "unconnected-(SV2-Pad4)") (class "Default")
      (node (ref "SV2") (pin "4") (pinfunction "4_4") (pintype "passive"))
    )
    (net (code "78") (name "unconnected-(SV2-Pad6)") (class "Default")
      (node (ref "SV2") (pin "6") (pinfunction "6_6") (pintype "passive"))
    )
    (net (code "79") (name "unconnected-(SV2-Pad8)") (class "Default")
      (node (ref "SV2") (pin "8") (pinfunction "8_8") (pintype "passive"))
    )
    (net (code "80") (name "unconnected-(SV2-Pad9)") (class "Default")
      (node (ref "SV2") (pin "9") (pinfunction "9_9") (pintype "passive"))
    )
    (net (code "81") (name "unconnected-(U$1-VREF-Pad5)") (class "Default")
      (node (ref "U$1") (pin "5") (pinfunction "VREF_5") (pintype "output"))
    )
    (net (code "82") (name "unconnected-(U1-PB0(ICP)-Pad14)") (class "Default")
      (node (ref "U1") (pin "14") (pinfunction "PB0(ICP)_14") (pintype "bidirectional"))
    )
    (net (code "83") (name "unconnected-(U1-PB1(OC1A)-Pad15)") (class "Default")
      (node (ref "U1") (pin "15") (pinfunction "PB1(OC1A)_15") (pintype "bidirectional"))
    )
    (net (code "84") (name "unconnected-(U1-PC3(ADC3)-Pad26)") (class "Default")
      (node (ref "U1") (pin "26") (pinfunction "PC3(ADC3)_26") (pintype "bidirectional"))
    )
    (net (code "85") (name "unconnected-(U1-PC4(ADC4{slash}SDA)-Pad27)") (class "Default")
      (node (ref "U1") (pin "27") (pinfunction "PC4(ADC4/SDA)_27") (pintype "bidirectional"))
    )
    (net (code "86") (name "unconnected-(U1-PD7(AIN1)-Pad13)") (class "Default")
      (node (ref "U1") (pin "13") (pinfunction "PD7(AIN1)_13") (pintype "bidirectional"))
    )
    (net (code "87") (name "unconnected-(U2A-CLKOUT-Pad3)") (class "Default")
      (node (ref "U2") (pin "3") (pinfunction "CLKOUT_3") (pintype "output"))
    )
    (net (code "88") (name "unconnected-(U2A-INT-Pad12)") (class "Default")
      (node (ref "U2") (pin "12") (pinfunction "INT_12") (pintype "output"))
    )
    (net (code "89") (name "unconnected-(U2A-RX0BF-Pad11)") (class "Default")
      (node (ref "U2") (pin "11") (pinfunction "RX0BF_11") (pintype "output"))
    )
    (net (code "90") (name "unconnected-(U2A-RX1BF-Pad10)") (class "Default")
      (node (ref "U2") (pin "10") (pinfunction "RX1BF_10") (pintype "output"))
    )
    (net (code "91") (name "unconnected-(U2A-TX0RTS-Pad4)") (class "Default")
      (node (ref "U2") (pin "4") (pinfunction "TX0RTS_4") (pintype "input"))
    )
    (net (code "92") (name "unconnected-(U2A-TX1RTS-Pad5)") (class "Default")
      (node (ref "U2") (pin "5") (pinfunction "TX1RTS_5") (pintype "input"))
    )
    (net (code "93") (name "unconnected-(U2A-TX2RTS-Pad6)") (class "Default")
      (node (ref "U2") (pin "6") (pinfunction "TX2RTS_6") (pintype "input"))
    )
  )
)
